# Connectors.net
KiCad netlist of a schematic drawn in Altium Designer
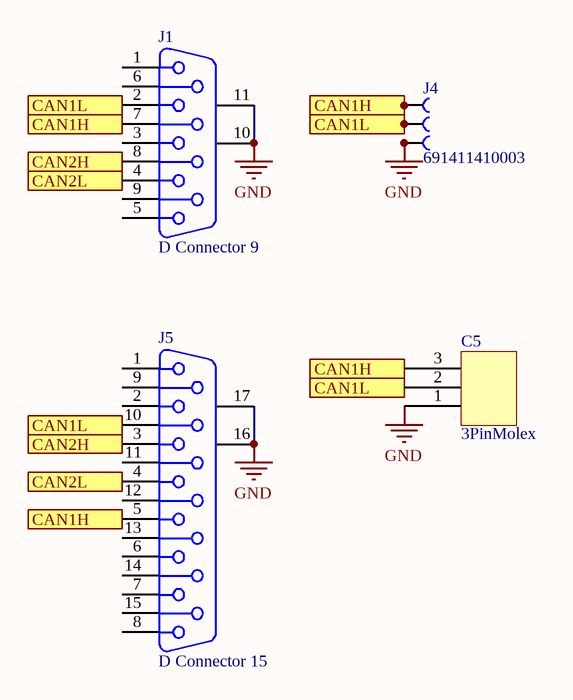
[diagram p0: Connectors.SchDoc]

(export (version "E")
  (design (tool "Eeschema 10.0.6"))
  (components
    (comp (ref "C5")
      (value "3PinMolex")
      (footprint "3PinMolex")
      (libsource (lib "3PinMolex") (part "3PinMolex"))
    )
    (comp (ref "J1")
      (value "D Connector 9")
      (footprint "DSUB1.385-2H9")
      (description "Receptacle Assembly, 9 Position, Right Angle")
      (fields (field (name "PUBLISHER") "Altium Limited"))
      (libsource (lib "Miscellaneous Connectors") (part "D Connector 9"))
    )
    (comp (ref "J4")
      (value "691411410003")
      (footprint "691411410003")
      (description "TERM BLK 3P SIDE ENT 7.62MM PCB")
      (fields (field (name "MF") "Wurth Electronics Inc."))
      (libsource (lib "691411410003") (part "691411410003"))
    )
    (comp (ref "J5")
      (value "D Connector 15")
      (footprint "DSUB1.385-2H15")
      (description "Receptacle Assembly, 15 Position, Right Angle")
      (fields (field (name "PUBLISHER") "Altium Limited"))
      (libsource (lib "Miscellaneous Connectors") (part "D Connector 15"))
    )
  )
  (nets
    (net (code "1") (name "/CAN1H") (class "Default")
      (node (ref "C5") (pin "3") (pintype "passive"))
      (node (ref "J1") (pin "7") (pinfunction "7_7") (pintype "passive"))
      (node (ref "J4") (pin "1") (pinfunction "1_1") (pintype "passive"))
      (node (ref "J4") (pin "A1") (pinfunction "1_A1") (pintype "passive"))
      (node (ref "J5") (pin "5") (pinfunction "5_5") (pintype "passive"))
    )
    (net (code "2") (name "/CAN1L") (class "Default")
      (node (ref "C5") (pin "2") (pintype "passive"))
      (node (ref "J1") (pin "2") (pinfunction "2_2") (pintype "passive"))
      (node (ref "J4") (pin "2") (pinfunction "2_2") (pintype "passive"))
      (node (ref "J4") (pin "A2") (pinfunction "2_A2") (pintype "passive"))
      (node (ref "J5") (pin "10") (pinfunction "10_10") (pintype "passive"))
    )
    (net (code "3") (name "/CAN2H") (class "Default")
      (node (ref "J1") (pin "8") (pinfunction "8_8") (pintype "passive"))
      (node (ref "J5") (pin "3") (pinfunction "3_3") (pintype "passive"))
    )
    (net (code "4") (name "/CAN2L") (class "Default")
      (node (ref "J1") (pin "4") (pinfunction "4_4") (pintype "passive"))
      (node (ref "J5") (pin "4") (pinfunction "4_4") (pintype "passive"))
    )
    (net (code "5") (name "GND") (class "Default")
      (node (ref "C5") (pin "1") (pintype "passive"))
      (node (ref "J1") (pin "10") (pinfunction "MH1_10") (pintype "passive"))
      (node (ref "J1") (pin "11") (pinfunction "MH2_11") (pintype "passive"))
      (node (ref "J4") (pin "3") (pinfunction "3_3") (pintype "passive"))
      (node (ref "J4") (pin "A3") (pinfunction "3_A3") (pintype "passive"))
      (node (ref "J5") (pin "16") (pinfunction "MH1_16") (pintype "passive"))
      (node (ref "J5") (pin "17") (pinfunction "MH2_17") (pintype "passive"))
    )
    (net (code "6") (name "unconnected-(J1-Pad1)") (class "Default")
      (node (ref "J1") (pin "1") (pinfunction "1_1") (pintype "passive"))
    )
    (net (code "7") (name "unconnected-(J1-Pad3)") (class "Default")
      (node (ref "J1") (pin "3") (pinfunction "3_3") (pintype "passive"))
    )
    (net (code "8") (name "unconnected-(J1-Pad5)") (class "Default")
      (node (ref "J1") (pin "5") (pinfunction "5_5") (pintype "passive"))
    )
    (net (code "9") (name "unconnected-(J1-Pad6)") (class "Default")
      (node (ref "J1") (pin "6") (pinfunction "6_6") (pintype "passive"))
    )
    (net (code "10") (name "unconnected-(J1-Pad9)") (class "Default")
      (node (ref "J1") (pin "9") (pinfunction "9_9") (pintype "passive"))
    )
    (net (code "11") (name "unconnected-(J5-Pad1)") (class "Default")
      (node (ref "J5") (pin "1") (pinfunction "1_1") (pintype "passive"))
    )
    (net (code "12") (name "unconnected-(J5-Pad2)") (class "Default")
      (node (ref "J5") (pin "2") (pinfunction "2_2") (pintype "passive"))
    )
    (net (code "13") (name "unconnected-(J5-Pad6)") (class "Default")
      (node (ref "J5") (pin "6") (pinfunction "6_6") (pintype "passive"))
    )
    (net (code "14") (name "unconnected-(J5-Pad7)") (class "Default")
      (node (ref "J5") (pin "7") (pinfunction "7_7") (pintype "passive"))
    )
    (net (code "15") (name "unconnected-(J5-Pad8)") (class "Default")
      (node (ref "J5") (pin "8") (pinfunction "8_8") (pintype "passive"))
    )
    (net (code "16") (name "unconnected-(J5-Pad9)") (class "Default")
      (node (ref "J5") (pin "9") (pinfunction "9_9") (pintype "passive"))
    )
    (net (code "17") (name "unconnected-(J5-Pad11)") (class "Default")
      (node (ref "J5") (pin "11") (pinfunction "11_11") (pintype "passive"))
    )
    (net (code "18") (name "unconnected-(J5-Pad12)") (class "Default")
      (node (ref "J5") (pin "12") (pinfunction "12_12") (pintype "passive"))
    )
    (net (code "19") (name "unconnected-(J5-Pad13)") (class "Default")
      (node (ref "J5") (pin "13") (pinfunction "13_13") (pintype "passive"))
    )
    (net (code "20") (name "unconnected-(J5-Pad14)") (class "Default")
      (node (ref "J5") (pin "14") (pinfunction "14_14") (pintype "passive"))
    )
    (net (code "21") (name "unconnected-(J5-Pad15)") (class "Default")
      (node (ref "J5") (pin "15") (pinfunction "15_15") (pintype "passive"))
    )
  )
)
